# low_filter.net
KiCad netlist of a schematic drawn in Altium Designer
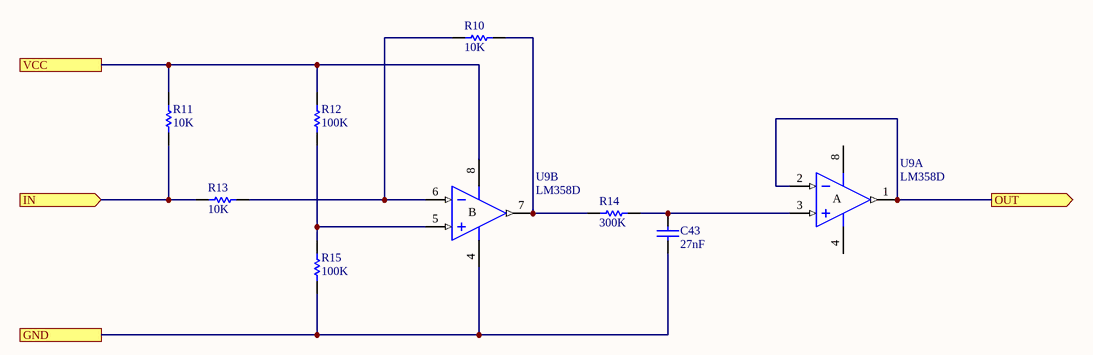
[diagram p0: low_filter.SchDoc]

(export (version "E")
  (design (tool "Eeschema 10.0.6"))
  (components
    (comp (ref "C43")
      (value "27nF")
      (footprint "C0603")
      (description "Capacitor, MLCC, 27nF, 16V, X7R, 10%, 0603, T=0,8mm")
      (fields
        (field (name "INTERNAL_PART_NUMBER") "MCD-00211")
        (field (name "MANUFACTURER_PART_NUMBER") "CC0603KRX7R7BB104")
        (field (name "PROVIDED_BY") "Subcon")
      )
      (libsource (lib "MCD_PARTS_database") (part "Capacitor"))
    )
    (comp (ref "R10")
      (value "10K")
      (footprint "R0603")
      (description "Resistor,10K,0603,1%,1/10W")
      (fields
        (field (name "INTERNAL_PART_NUMBER") "MCD-00220")
        (field (name "MANUFACTURER_PART_NUMBER") "RC0603FR-0710KL")
        (field (name "PROVIDED_BY") "Subcon")
      )
      (libsource (lib "MCD_PARTS_database") (part "Resistor"))
    )
    (comp (ref "R11")
      (value "10K")
      (footprint "R0603")
      (description "Resistor,10K,0603,1%,1/10W")
      (fields
        (field (name "INTERNAL_PART_NUMBER") "MCD-00220")
        (field (name "MANUFACTURER_PART_NUMBER") "RC0603FR-0710KL")
        (field (name "PROVIDED_BY") "Subcon")
      )
      (libsource (lib "MCD_PARTS_database") (part "Resistor"))
    )
    (comp (ref "R12")
      (value "100K")
      (footprint "R0603")
      (description "Resistor,100K,0603,1%,1/10W")
      (fields
        (field (name "INTERNAL_PART_NUMBER") "MCD-00220")
        (field (name "MANUFACTURER_PART_NUMBER") "RC0603FR-0710KL")
        (field (name "PROVIDED_BY") "Subcon")
      )
      (libsource (lib "MCD_PARTS_database") (part "Resistor"))
    )
    (comp (ref "R13")
      (value "10K")
      (footprint "R0603")
      (description "Resistor,10K,0603,1%,1/10W")
      (fields
        (field (name "INTERNAL_PART_NUMBER") "MCD-00220")
        (field (name "MANUFACTURER_PART_NUMBER") "RC0603FR-0710KL")
        (field (name "PROVIDED_BY") "Subcon")
      )
      (libsource (lib "MCD_PARTS_database") (part "Resistor"))
    )
    (comp (ref "R14")
      (value "300K")
      (footprint "R0603")
      (description "Resistor,300K,0603,1%,1/10W")
      (fields
        (field (name "INTERNAL_PART_NUMBER") "MCD-00220")
        (field (name "MANUFACTURER_PART_NUMBER") "RC0603FR-0710KL")
        (field (name "PROVIDED_BY") "Subcon")
      )
      (libsource (lib "MCD_PARTS_database") (part "Resistor"))
    )
    (comp (ref "R15")
      (value "100K")
      (footprint "R0603")
      (description "Resistor,100K,0603,1%,1/10W")
      (fields
        (field (name "INTERNAL_PART_NUMBER") "MCD-00220")
        (field (name "MANUFACTURER_PART_NUMBER") "RC0603FR-0710KL")
        (field (name "PROVIDED_BY") "Subcon")
      )
      (libsource (lib "MCD_PARTS_database") (part "Resistor"))
    )
    (comp (ref "U9")
      (value "LM358D")
      (footprint "SO8_N")
      (description "Dual Low-Power Operational Amplifier")
      (fields (field (name "PUBLISHER") "Altium Limited"))
      (libsource (lib "ST Operational Amplifier") (part "LM358D"))
    )
  )
  (nets
    (net (code "1") (name "/GND") (class "Default")
      (node (ref "C43") (pin "1") (pinfunction "1_1") (pintype "passive"))
      (node (ref "R15") (pin "2") (pinfunction "2_2") (pintype "passive"))
      (node (ref "U9") (pin "4") (pinfunction "V-_4") (pintype "power_in"))
    )
    (net (code "2") (name "/IN") (class "Default")
      (node (ref "R11") (pin "2") (pinfunction "2_2") (pintype "passive"))
      (node (ref "R13") (pin "1") (pinfunction "1_1") (pintype "passive"))
    )
    (net (code "3") (name "/OUT") (class "Default")
      (node (ref "U9") (pin "1") (pinfunction "OUT_1") (pintype "output"))
      (node (ref "U9") (pin "2") (pinfunction "IN-_2") (pintype "input"))
    )
    (net (code "4") (name "/VCC") (class "Default")
      (node (ref "R11") (pin "1") (pinfunction "1_1") (pintype "passive"))
      (node (ref "R12") (pin "1") (pinfunction "1_1") (pintype "passive"))
      (node (ref "U9") (pin "8") (pinfunction "V+_8") (pintype "power_in"))
    )
    (net (code "5") (name "Net-(U9A-IN+)") (class "Default")
      (node (ref "C43") (pin "2") (pinfunction "2_2") (pintype "passive"))
      (node (ref "R14") (pin "2") (pinfunction "2_2") (pintype "passive"))
      (node (ref "U9") (pin "3") (pinfunction "IN+_3") (pintype "input"))
    )
    (net (code "6") (name "Net-(U9B-IN+)") (class "Default")
      (node (ref "R12") (pin "2") (pinfunction "2_2") (pintype "passive"))
      (node (ref "R15") (pin "1") (pinfunction "1_1") (pintype "passive"))
      (node (ref "U9") (pin "5") (pinfunction "IN+_5") (pintype "input"))
    )
    (net (code "7") (name "Net-(U9B-IN-)") (class "Default")
      (node (ref "R10") (pin "1") (pinfunction "1_1") (pintype "passive"))
      (node (ref "R13") (pin "2") (pinfunction "2_2") (pintype "passive"))
      (node (ref "U9") (pin "6") (pinfunction "IN-_6") (pintype "input"))
    )
    (net (code "8") (name "Net-(U9B-OUT)") (class "Default")
      (node (ref "R10") (pin "2") (pinfunction "2_2") (pintype "passive"))
      (node (ref "R14") (pin "1") (pinfunction "1_1") (pintype "passive"))
      (node (ref "U9") (pin "7") (pinfunction "OUT_7") (pintype "output"))
    )
    (net (code "9") (name "unconnected-(U9A-V+-Pad8)") (class "Default")
      (node (ref "U9") (pin "8") (pinfunction "V+_8") (pintype "power_in"))
    )
    (net (code "10") (name "unconnected-(U9A-V--Pad4)") (class "Default")
      (node (ref "U9") (pin "4") (pinfunction "V-_4") (pintype "power_in"))
    )
  )
)
